# atx_power_control.net
KiCad netlist of a schematic drawn in EAGLE
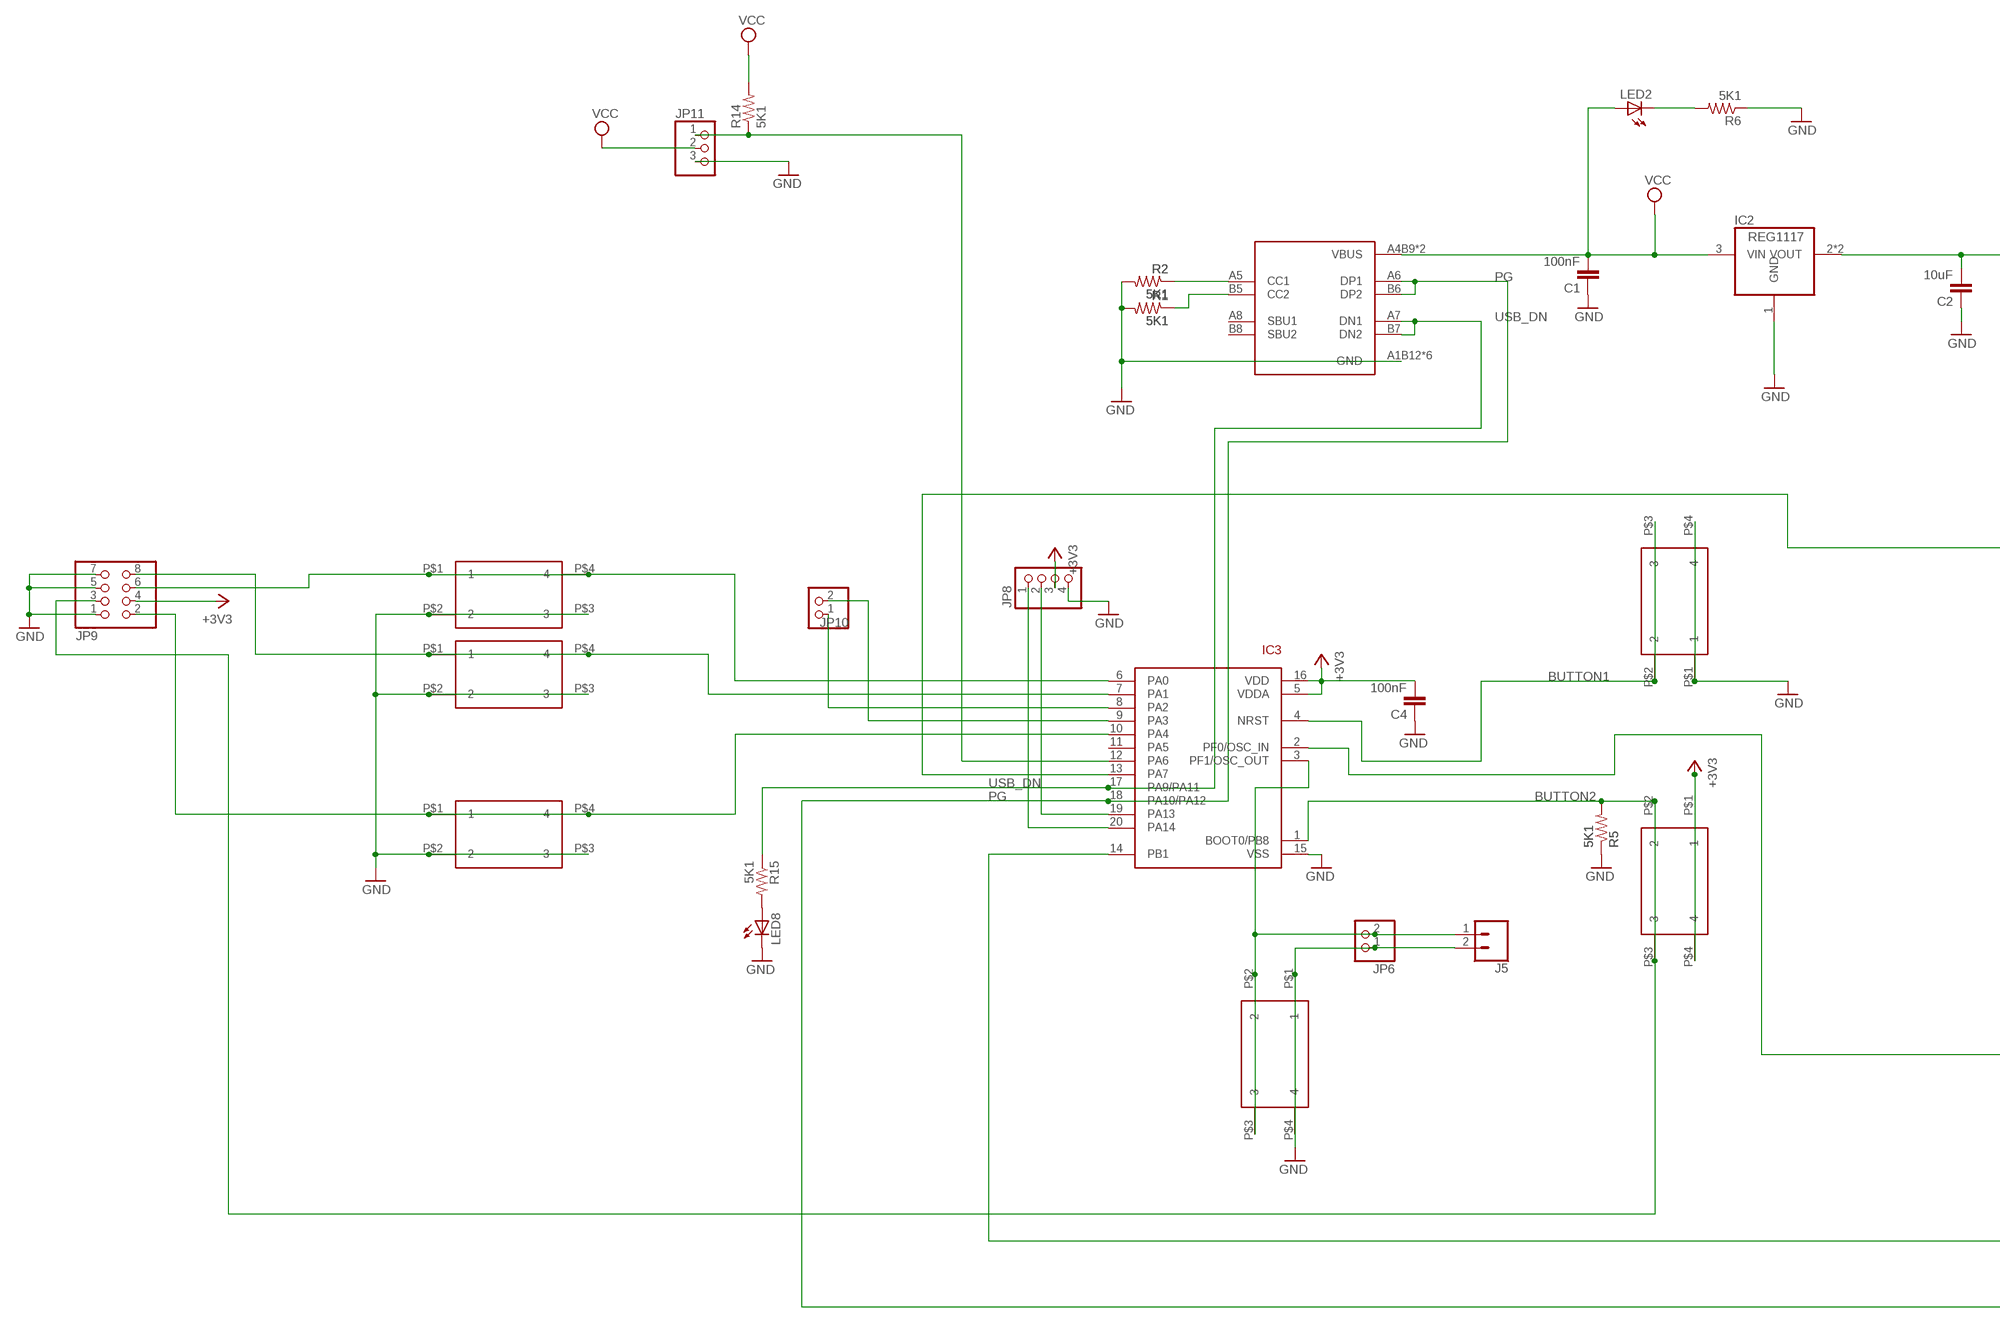
[diagram p0: schematic, sheet 1, part 1 of 2]
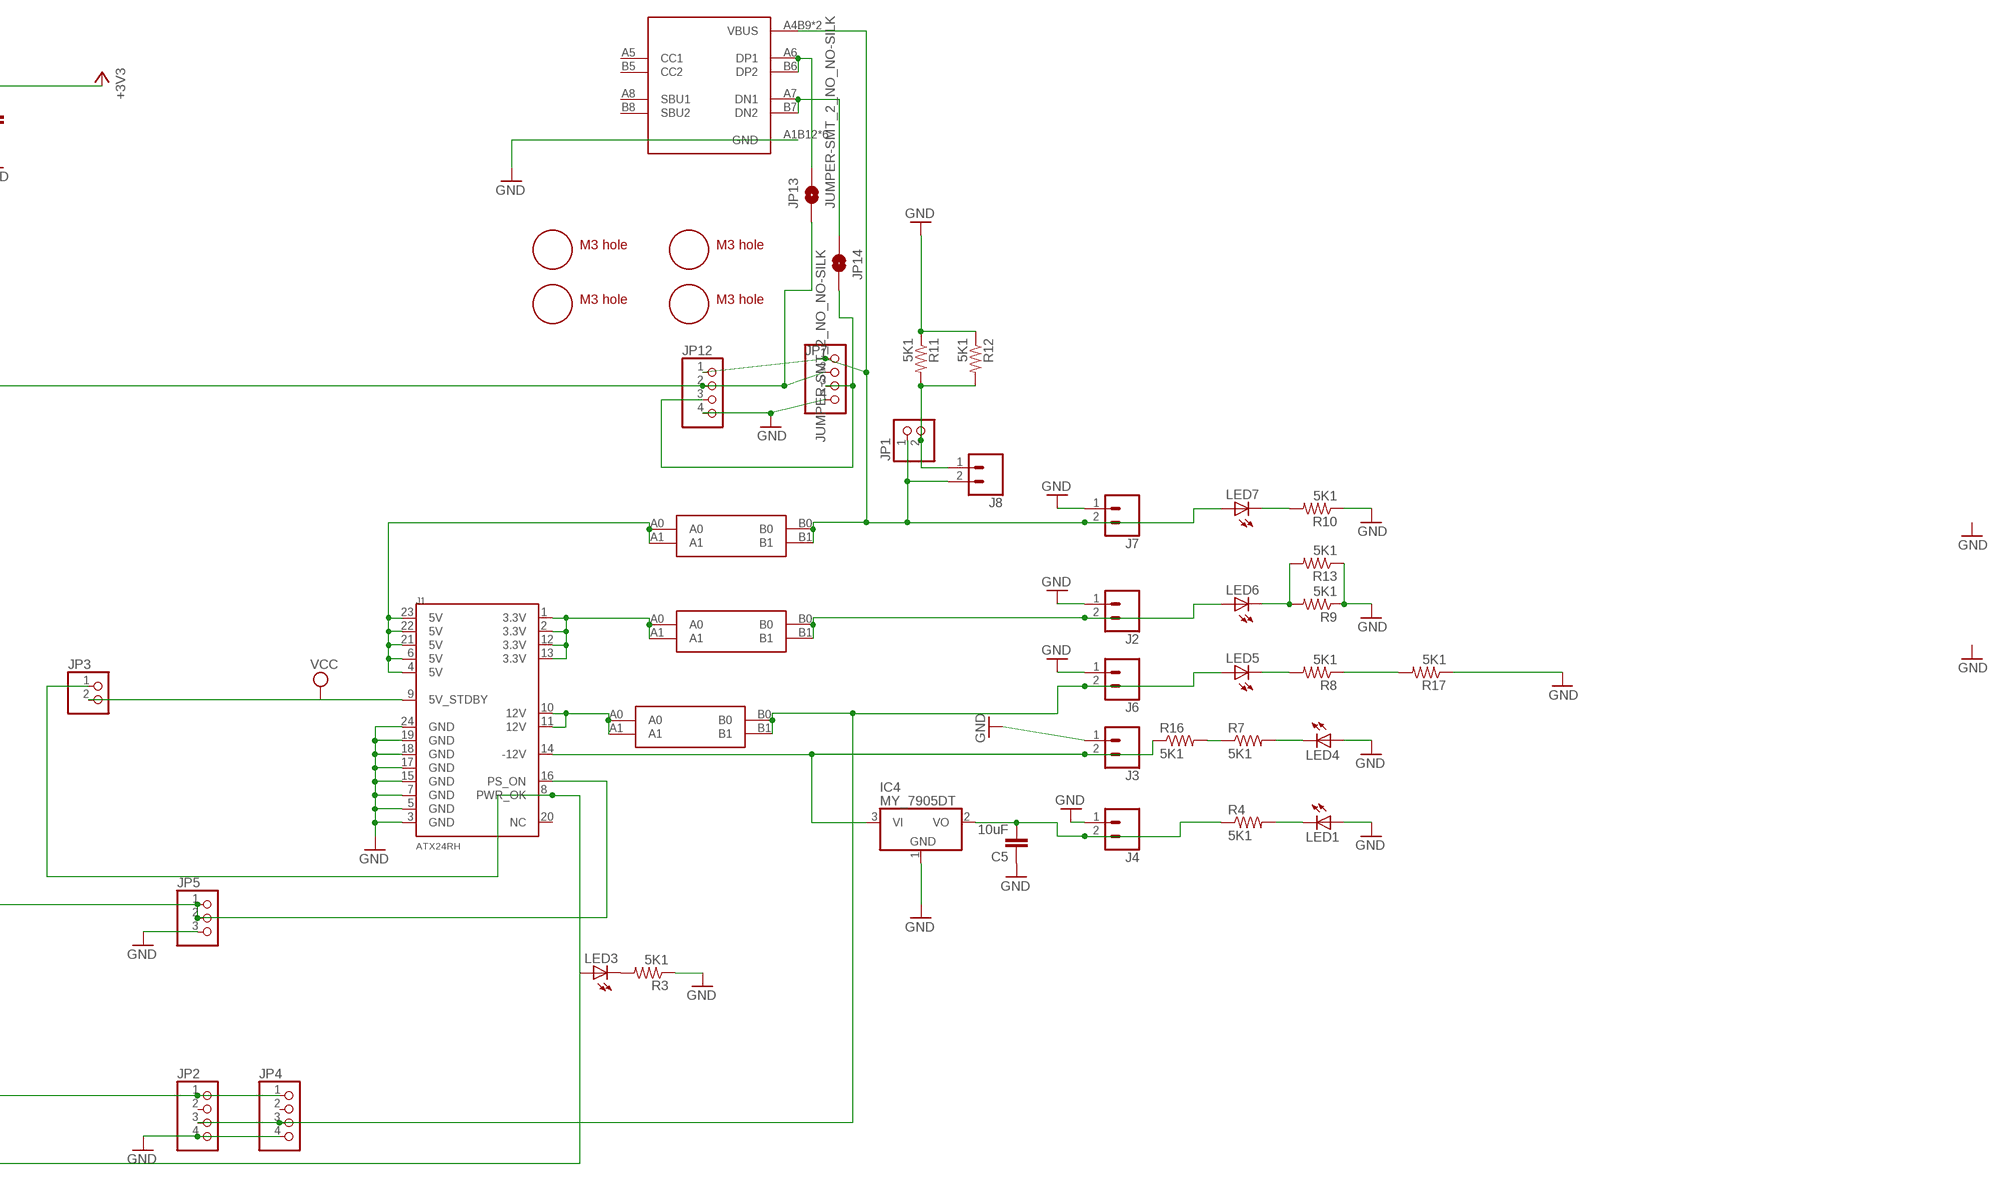
[diagram p1: schematic, sheet 1, part 2 of 2]

(export (version "E")
  (design (tool "Eeschema 10.0.6"))
  (components
    (comp (ref "C1")
      (value "100nF")
      (footprint "eagle-import:0805$1")
      (libsource (lib "eagle-import") (part "CAP0805"))
    )
    (comp (ref "C2")
      (value "10uF")
      (footprint "eagle-import:0805$1")
      (libsource (lib "eagle-import") (part "CAP0805"))
    )
    (comp (ref "C4")
      (value "100nF")
      (footprint "eagle-import:0805$1")
      (libsource (lib "eagle-import") (part "CAP0805"))
    )
    (comp (ref "C5")
      (value "10uF")
      (footprint "eagle-import:0805$1")
      (libsource (lib "eagle-import") (part "CAP0805"))
    )
    (comp (ref "IC2")
      (value "REG1117")
      (footprint "eagle-import:SOT223")
      (fields (field (name "MF") "TEXAS INSTRUMENTS") (field (name "MPN") "REG1117FAKTTT"))
      (libsource (lib "eagle-import") (part "REG1117"))
    )
    (comp (ref "IC3")
      (value "STM32F042F4")
      (footprint "eagle-import:TSSOP20")
      (libsource (lib "eagle-import") (part "STM32F042F4"))
    )
    (comp (ref "IC4")
      (value "MY_7905DT")
      (footprint "eagle-import:ADAFRUIT_TO252")
      (libsource (lib "eagle-import") (part "MY_7905DT"))
    )
    (comp (ref "J1")
      (value "ATX24RH")
      (footprint "eagle-import:ATX24_RIGHT_ANGLE")
      (libsource (lib "eagle-import") (part "ATX24RH"))
    )
    (comp (ref "J2")
      (value "CONN_023.5MM")
      (footprint "eagle-import:SCREWTERMINAL-3.5MM-2")
      (libsource (lib "eagle-import") (part "CONN_023.5MM"))
    )
    (comp (ref "J3")
      (value "CONN_023.5MM")
      (footprint "eagle-import:SCREWTERMINAL-3.5MM-2")
      (libsource (lib "eagle-import") (part "CONN_023.5MM"))
    )
    (comp (ref "J4")
      (value "CONN_023.5MM")
      (footprint "eagle-import:SCREWTERMINAL-3.5MM-2")
      (libsource (lib "eagle-import") (part "CONN_023.5MM"))
    )
    (comp (ref "J5")
      (value "CONN_023.5MM")
      (footprint "eagle-import:SCREWTERMINAL-3.5MM-2")
      (libsource (lib "eagle-import") (part "CONN_023.5MM"))
    )
    (comp (ref "J6")
      (value "CONN_023.5MM")
      (footprint "eagle-import:SCREWTERMINAL-3.5MM-2")
      (libsource (lib "eagle-import") (part "CONN_023.5MM"))
    )
    (comp (ref "J7")
      (value "CONN_023.5MM-NO_SILK")
      (footprint "eagle-import:SCREWTERMINAL-3.5MM-2-NS")
      (libsource (lib "eagle-import") (part "CONN_023.5MM-NO_SILK"))
    )
    (comp (ref "J8")
      (value "CONN_023.5MM")
      (footprint "eagle-import:SCREWTERMINAL-3.5MM-2")
      (libsource (lib "eagle-import") (part "CONN_023.5MM"))
    )
    (comp (ref "JP1")
      (value "PINHD-1X2")
      (footprint "eagle-import:1X02")
      (libsource (lib "eagle-import") (part "pinhead_325_PINHD-1X2"))
    )
    (comp (ref "JP2")
      (value "PINHD-1X4")
      (footprint "eagle-import:1X04")
      (libsource (lib "eagle-import") (part "PINHD-1X4"))
    )
    (comp (ref "JP3")
      (value "PINHD-1X2")
      (footprint "eagle-import:1X02")
      (libsource (lib "eagle-import") (part "pinhead_325_PINHD-1X2"))
    )
    (comp (ref "JP4")
      (value "PINHD-1X4")
      (footprint "eagle-import:1X04")
      (libsource (lib "eagle-import") (part "PINHD-1X4"))
    )
    (comp (ref "JP5")
      (value "PINHD-1X3:1")
      (footprint "eagle-import:1X03")
      (libsource (lib "eagle-import") (part "PINHD-1X3?{colon}1"))
    )
    (comp (ref "JP6")
      (value "PINHD-1X2")
      (footprint "eagle-import:1X02")
      (libsource (lib "eagle-import") (part "PINHD-1X2"))
    )
    (comp (ref "JP7")
      (value "PINHD-1X6")
      (footprint "eagle-import:1X06")
      (libsource (lib "eagle-import") (part "PINHD-1X6"))
    )
    (comp (ref "JP8")
      (value "PINHD-1X4")
      (footprint "eagle-import:1X04")
      (libsource (lib "eagle-import") (part "PINHD-1X4"))
    )
    (comp (ref "JP9")
      (value "PINHD-2X4")
      (footprint "eagle-import:2X04")
      (libsource (lib "eagle-import") (part "PINHD-2X4"))
    )
    (comp (ref "JP10")
      (value "PINHD-1X2")
      (footprint "eagle-import:1X02")
      (libsource (lib "eagle-import") (part "pinhead_325_PINHD-1X2"))
    )
    (comp (ref "JP11")
      (value "PINHD-1X3CB")
      (footprint "eagle-import:1X03-CLEANBIG")
      (libsource (lib "eagle-import") (part "PINHD-1X3CB"))
    )
    (comp (ref "JP12")
      (value "PINHD-1X6")
      (footprint "eagle-import:1X06")
      (libsource (lib "eagle-import") (part "PINHD-1X6"))
    )
    (comp (ref "JP13")
      (value "JUMPER-SMT_2_NO_NO-SILK")
      (footprint "eagle-import:SMT-JUMPER_2_NO_NO-SILK")
      (libsource (lib "eagle-import") (part "JUMPER-SMT_2_NO_NO-SILK"))
    )
    (comp (ref "JP14")
      (value "JUMPER-SMT_2_NO_NO-SILK")
      (footprint "eagle-import:SMT-JUMPER_2_NO_NO-SILK")
      (libsource (lib "eagle-import") (part "JUMPER-SMT_2_NO_NO-SILK"))
    )
    (comp (ref "LED1")
      (value "LEDCHIP-LED0805")
      (footprint "eagle-import:CHIP-LED0805")
      (libsource (lib "eagle-import") (part "LEDCHIP-LED0805"))
    )
    (comp (ref "LED2")
      (value "LEDCHIP-LED0805")
      (footprint "eagle-import:CHIP-LED0805")
      (libsource (lib "eagle-import") (part "LEDCHIP-LED0805"))
    )
    (comp (ref "LED3")
      (value "LEDCHIP-LED0805")
      (footprint "eagle-import:CHIP-LED0805")
      (libsource (lib "eagle-import") (part "LEDCHIP-LED0805"))
    )
    (comp (ref "LED4")
      (value "LEDCHIP-LED0805")
      (footprint "eagle-import:CHIP-LED0805")
      (libsource (lib "eagle-import") (part "LEDCHIP-LED0805"))
    )
    (comp (ref "LED5")
      (value "LEDCHIP-LED0805")
      (footprint "eagle-import:CHIP-LED0805")
      (libsource (lib "eagle-import") (part "LEDCHIP-LED0805"))
    )
    (comp (ref "LED6")
      (value "LEDCHIP-LED0805")
      (footprint "eagle-import:CHIP-LED0805")
      (libsource (lib "eagle-import") (part "LEDCHIP-LED0805"))
    )
    (comp (ref "LED7")
      (value "LEDCHIP-LED0805")
      (footprint "eagle-import:CHIP-LED0805")
      (libsource (lib "eagle-import") (part "LEDCHIP-LED0805"))
    )
    (comp (ref "LED8")
      (value "LEDCHIP-LED0805")
      (footprint "eagle-import:CHIP-LED0805")
      (libsource (lib "eagle-import") (part "LEDCHIP-LED0805"))
    )
    (comp (ref "R1")
      (value "5K1")
      (footprint "eagle-import:0805")
      (libsource (lib "eagle-import") (part "atx_power_control_RESISTOR0805-RES"))
    )
    (comp (ref "R2")
      (value "5K1")
      (footprint "eagle-import:0805")
      (libsource (lib "eagle-import") (part "atx_power_control_RESISTOR0805-RES"))
    )
    (comp (ref "R3")
      (value "5K1")
      (footprint "eagle-import:0805")
      (libsource (lib "eagle-import") (part "atx_power_control_RESISTOR0805-RES"))
    )
    (comp (ref "R4")
      (value "5K1")
      (footprint "eagle-import:0805")
      (libsource (lib "eagle-import") (part "RESISTOR0805-RES"))
    )
    (comp (ref "R5")
      (value "5K1")
      (footprint "eagle-import:0805")
      (libsource (lib "eagle-import") (part "atx_power_control_RESISTOR0805-RES"))
    )
    (comp (ref "R6")
      (value "5K1")
      (footprint "eagle-import:0805")
      (libsource (lib "eagle-import") (part "atx_power_control_RESISTOR0805-RES"))
    )
    (comp (ref "R7")
      (value "5K1")
      (footprint "eagle-import:0805")
      (libsource (lib "eagle-import") (part "RESISTOR0805-RES"))
    )
    (comp (ref "R8")
      (value "5K1")
      (footprint "eagle-import:0805")
      (libsource (lib "eagle-import") (part "atx_power_control_RESISTOR0805-RES"))
    )
    (comp (ref "R9")
      (value "5K1")
      (footprint "eagle-import:0805")
      (libsource (lib "eagle-import") (part "atx_power_control_RESISTOR0805-RES"))
    )
    (comp (ref "R10")
      (value "5K1")
      (footprint "eagle-import:0805")
      (libsource (lib "eagle-import") (part "atx_power_control_RESISTOR0805-RES"))
    )
    (comp (ref "R11")
      (value "5K1")
      (footprint "eagle-import:0805")
      (libsource (lib "eagle-import") (part "atx_power_control_RESISTOR0805-RES"))
    )
    (comp (ref "R12")
      (value "5K1")
      (footprint "eagle-import:0805")
      (libsource (lib "eagle-import") (part "atx_power_control_RESISTOR0805-RES"))
    )
    (comp (ref "R13")
      (value "5K1")
      (footprint "eagle-import:0805")
      (libsource (lib "eagle-import") (part "atx_power_control_RESISTOR0805-RES"))
    )
    (comp (ref "R14")
      (value "5K1")
      (footprint "eagle-import:0805")
      (libsource (lib "eagle-import") (part "atx_power_control_RESISTOR0805-RES"))
    )
    (comp (ref "R15")
      (value "5K1")
      (footprint "eagle-import:0805")
      (libsource (lib "eagle-import") (part "atx_power_control_RESISTOR0805-RES"))
    )
    (comp (ref "R16")
      (value "5K1")
      (footprint "eagle-import:0805")
      (libsource (lib "eagle-import") (part "RESISTOR0805-RES"))
    )
    (comp (ref "R17")
      (value "5K1")
      (footprint "eagle-import:0805")
      (libsource (lib "eagle-import") (part "atx_power_control_RESISTOR0805-RES"))
    )
    (comp (ref "SW1")
      (value "324_SW")
      (footprint "eagle-import:342_SWICH_FOOT")
      (libsource (lib "eagle-import") (part "324_SW"))
    )
    (comp (ref "SW2")
      (value "324_SW")
      (footprint "eagle-import:342_SWICH_FOOT")
      (libsource (lib "eagle-import") (part "324_SW"))
    )
    (comp (ref "SW3")
      (value "324_SW")
      (footprint "eagle-import:342_SWICH_FOOT")
      (libsource (lib "eagle-import") (part "324_SW"))
    )
    (comp (ref "SW4")
      (value "324_SW")
      (footprint "eagle-import:342_SWICH_FOOT")
      (libsource (lib "eagle-import") (part "324_SW"))
    )
    (comp (ref "SW5")
      (value "324_SW")
      (footprint "eagle-import:342_SWICH_FOOT")
      (libsource (lib "eagle-import") (part "324_SW"))
    )
    (comp (ref "SW7")
      (value "324_SW")
      (footprint "eagle-import:342_SWICH_FOOT")
      (libsource (lib "eagle-import") (part "324_SW"))
    )
    (comp (ref "U$1")
      (value "M3_MOUNTING_HOLE")
      (footprint "eagle-import:M3_MOUNTING_HOLE_PACK")
      (libsource (lib "eagle-import") (part "M3_MOUNTING_HOLE"))
    )
    (comp (ref "U$2")
      (value "M3_MOUNTING_HOLE")
      (footprint "eagle-import:M3_MOUNTING_HOLE_PACK")
      (libsource (lib "eagle-import") (part "M3_MOUNTING_HOLE"))
    )
    (comp (ref "U$3")
      (value "M3_MOUNTING_HOLE")
      (footprint "eagle-import:M3_MOUNTING_HOLE_PACK")
      (libsource (lib "eagle-import") (part "M3_MOUNTING_HOLE"))
    )
    (comp (ref "U$5")
      (value "CAR_FUSE_HOLDER3IN1")
      (footprint "eagle-import:FUSE_HOLDER_3IN1")
      (libsource (lib "eagle-import") (part "CAR_FUSE_HOLDER3IN1"))
    )
    (comp (ref "U$7")
      (value "CAR_FUSE_HOLDER3IN1")
      (footprint "eagle-import:FUSE_HOLDER_3IN1")
      (libsource (lib "eagle-import") (part "CAR_FUSE_HOLDER3IN1"))
    )
    (comp (ref "U$8")
      (value "CAR_FUSE_HOLDER3IN1")
      (footprint "eagle-import:FUSE_HOLDER_3IN1")
      (libsource (lib "eagle-import") (part "CAR_FUSE_HOLDER3IN1"))
    )
    (comp (ref "U$10")
      (value "M3_MOUNTING_HOLE")
      (footprint "eagle-import:M3_MOUNTING_HOLE_PACK")
      (libsource (lib "eagle-import") (part "M3_MOUNTING_HOLE"))
    )
    (comp (ref "U1")
      (value "USBC_16P")
      (footprint "eagle-import:USBC_16P_FOOT")
      (libsource (lib "eagle-import") (part "USBC_16P"))
    )
    (comp (ref "U2")
      (value "USBC_16P")
      (footprint "eagle-import:USBC_16P_FOOT")
      (libsource (lib "eagle-import") (part "USBC_16P"))
    )
  )
  (nets
    (net (code "1") (name "+3V3") (class "Default")
      (node (ref "C2") (pin "2") (pinfunction "2_2") (pintype "passive"))
      (node (ref "C4") (pin "2") (pinfunction "2_2") (pintype "passive"))
      (node (ref "IC2") (pin "2") (pinfunction "VOUT_2") (pintype "output"))
      (node (ref "IC2") (pin "4") (pinfunction "VOUT_4") (pintype "output"))
      (node (ref "IC3") (pin "16") (pinfunction "VDD_16") (pintype "bidirectional"))
      (node (ref "IC3") (pin "5") (pinfunction "VDDA_5") (pintype "bidirectional"))
      (node (ref "JP8") (pin "3") (pinfunction "3_3") (pintype "passive"))
      (node (ref "JP9") (pin "4") (pinfunction "4_4") (pintype "passive"))
      (node (ref "SW4") (pin "P$1") (pinfunction "1_P$1") (pintype "bidirectional"))
      (node (ref "SW4") (pin "P$4") (pinfunction "4_P$4") (pintype "bidirectional"))
    )
    (net (code "2") (name "/BUTTON1") (class "Default")
      (node (ref "IC3") (pin "4") (pinfunction "NRST_4") (pintype "bidirectional"))
      (node (ref "SW3") (pin "P$2") (pinfunction "2_P$2") (pintype "bidirectional"))
      (node (ref "SW3") (pin "P$3") (pinfunction "3_P$3") (pintype "bidirectional"))
    )
    (net (code "3") (name "/BUTTON2") (class "Default")
      (node (ref "IC3") (pin "1") (pinfunction "BOOT0/PB8_1") (pintype "bidirectional"))
      (node (ref "JP9") (pin "3") (pinfunction "3_3") (pintype "passive"))
      (node (ref "R5") (pin "2") (pinfunction "2_2") (pintype "passive"))
      (node (ref "SW4") (pin "P$2") (pinfunction "2_P$2") (pintype "bidirectional"))
      (node (ref "SW4") (pin "P$3") (pinfunction "3_P$3") (pintype "bidirectional"))
    )
    (net (code "4") (name "/PG") (class "Default")
      (node (ref "IC3") (pin "18") (pinfunction "PA10/PA12_18") (pintype "bidirectional"))
      (node (ref "J1") (pin "8") (pinfunction "PWR_OK_8") (pintype "bidirectional"))
      (node (ref "JP3") (pin "1") (pinfunction "1_1") (pintype "passive"))
      (node (ref "LED3") (pin "A") (pinfunction "A_A") (pintype "passive"))
      (node (ref "U2") (pin "A6") (pinfunction "DP1_A6") (pintype "bidirectional"))
      (node (ref "U2") (pin "B6") (pinfunction "DP2_B6") (pintype "bidirectional"))
    )
    (net (code "5") (name "/USB_DN") (class "Default")
      (node (ref "IC3") (pin "17") (pinfunction "PA9/PA11_17") (pintype "bidirectional"))
      (node (ref "R15") (pin "1") (pinfunction "1_1") (pintype "passive"))
      (node (ref "U2") (pin "A7") (pinfunction "DN1_A7") (pintype "bidirectional"))
      (node (ref "U2") (pin "B7") (pinfunction "DN2_B7") (pintype "bidirectional"))
    )
    (net (code "6") (name "GND") (class "Default")
      (node (ref "C1") (pin "1") (pinfunction "1_1") (pintype "passive"))
      (node (ref "C2") (pin "1") (pinfunction "1_1") (pintype "passive"))
      (node (ref "C4") (pin "1") (pinfunction "1_1") (pintype "passive"))
      (node (ref "C5") (pin "1") (pinfunction "1_1") (pintype "passive"))
      (node (ref "IC2") (pin "1") (pinfunction "GND_1") (pintype "power_in"))
      (node (ref "IC3") (pin "15") (pinfunction "VSS_15") (pintype "bidirectional"))
      (node (ref "IC4") (pin "1") (pinfunction "GND_1") (pintype "passive"))
      (node (ref "J1") (pin "15") (pinfunction "GND_15") (pintype "bidirectional"))
      (node (ref "J1") (pin "17") (pinfunction "GND_17") (pintype "bidirectional"))
      (node (ref "J1") (pin "18") (pinfunction "GND_18") (pintype "bidirectional"))
      (node (ref "J1") (pin "19") (pinfunction "GND_19") (pintype "bidirectional"))
      (node (ref "J1") (pin "24") (pinfunction "GND_24") (pintype "bidirectional"))
      (node (ref "J1") (pin "3") (pinfunction "GND_3") (pintype "bidirectional"))
      (node (ref "J1") (pin "5") (pinfunction "GND_5") (pintype "bidirectional"))
      (node (ref "J1") (pin "7") (pinfunction "GND_7") (pintype "bidirectional"))
      (node (ref "J2") (pin "1") (pinfunction "1_1") (pintype "passive"))
      (node (ref "J3") (pin "1") (pinfunction "1_1") (pintype "passive"))
      (node (ref "J4") (pin "1") (pinfunction "1_1") (pintype "passive"))
      (node (ref "J5") (pin "2") (pinfunction "2_2") (pintype "passive"))
      (node (ref "J6") (pin "1") (pinfunction "1_1") (pintype "passive"))
      (node (ref "J7") (pin "1") (pinfunction "1_1") (pintype "passive"))
      (node (ref "JP11") (pin "3") (pinfunction "3_3") (pintype "passive"))
      (node (ref "JP12") (pin "4") (pinfunction "4_4") (pintype "passive"))
      (node (ref "JP2") (pin "4") (pinfunction "4_4") (pintype "passive"))
      (node (ref "JP4") (pin "4") (pinfunction "4_4") (pintype "passive"))
      (node (ref "JP5") (pin "3") (pinfunction "3_3") (pintype "passive"))
      (node (ref "JP6") (pin "1") (pinfunction "1_1") (pintype "passive"))
      (node (ref "JP7") (pin "4") (pinfunction "4_4") (pintype "passive"))
      (node (ref "JP8") (pin "4") (pinfunction "4_4") (pintype "passive"))
      (node (ref "JP9") (pin "1") (pinfunction "1_1") (pintype "passive"))
      (node (ref "JP9") (pin "5") (pinfunction "5_5") (pintype "passive"))
      (node (ref "JP9") (pin "7") (pinfunction "7_7") (pintype "passive"))
      (node (ref "LED1") (pin "A") (pinfunction "A_A") (pintype "passive"))
      (node (ref "LED4") (pin "A") (pinfunction "A_A") (pintype "passive"))
      (node (ref "LED8") (pin "C") (pinfunction "C_C") (pintype "passive"))
      (node (ref "R1") (pin "2") (pinfunction "2_2") (pintype "passive"))
      (node (ref "R10") (pin "1") (pinfunction "1_1") (pintype "passive"))
      (node (ref "R11") (pin "1") (pinfunction "1_1") (pintype "passive"))
      (node (ref "R12") (pin "1") (pinfunction "1_1") (pintype "passive"))
      (node (ref "R13") (pin "1") (pinfunction "1_1") (pintype "passive"))
      (node (ref "R17") (pin "1") (pinfunction "1_1") (pintype "passive"))
      (node (ref "R2") (pin "2") (pinfunction "2_2") (pintype "passive"))
      (node (ref "R3") (pin "1") (pinfunction "1_1") (pintype "passive"))
      (node (ref "R5") (pin "1") (pinfunction "1_1") (pintype "passive"))
      (node (ref "R6") (pin "1") (pinfunction "1_1") (pintype "passive"))
      (node (ref "R9") (pin "1") (pinfunction "1_1") (pintype "passive"))
      (node (ref "SW1") (pin "P$1") (pinfunction "1_P$1") (pintype "bidirectional"))
      (node (ref "SW1") (pin "P$4") (pinfunction "4_P$4") (pintype "bidirectional"))
      (node (ref "SW2") (pin "P$2") (pinfunction "2_P$2") (pintype "bidirectional"))
      (node (ref "SW2") (pin "P$3") (pinfunction "3_P$3") (pintype "bidirectional"))
      (node (ref "SW3") (pin "P$1") (pinfunction "1_P$1") (pintype "bidirectional"))
      (node (ref "SW3") (pin "P$4") (pinfunction "4_P$4") (pintype "bidirectional"))
      (node (ref "SW5") (pin "P$2") (pinfunction "2_P$2") (pintype "bidirectional"))
      (node (ref "SW5") (pin "P$3") (pinfunction "3_P$3") (pintype "bidirectional"))
      (node (ref "SW7") (pin "P$2") (pinfunction "2_P$2") (pintype "bidirectional"))
      (node (ref "SW7") (pin "P$3") (pinfunction "3_P$3") (pintype "bidirectional"))
      (node (ref "U1") (pin "A1B12") (pinfunction "GND_A1B12") (pintype "bidirectional"))
      (node (ref "U1") (pin "B11A12") (pinfunction "GND_B11A12") (pintype "bidirectional"))
      (node (ref "U1") (pin "P$13") (pinfunction "GND_P$13") (pintype "bidirectional"))
      (node (ref "U1") (pin "P$14") (pinfunction "GND_P$14") (pintype "bidirectional"))
      (node (ref "U1") (pin "P$15") (pinfunction "GND_P$15") (pintype "bidirectional"))
      (node (ref "U1") (pin "P$16") (pinfunction "GND_P$16") (pintype "bidirectional"))
      (node (ref "U2") (pin "A1B12") (pinfunction "GND_A1B12") (pintype "bidirectional"))
      (node (ref "U2") (pin "B11A12") (pinfunction "GND_B11A12") (pintype "bidirectional"))
      (node (ref "U2") (pin "P$13") (pinfunction "GND_P$13") (pintype "bidirectional"))
      (node (ref "U2") (pin "P$14") (pinfunction "GND_P$14") (pintype "bidirectional"))
      (node (ref "U2") (pin "P$15") (pinfunction "GND_P$15") (pintype "bidirectional"))
      (node (ref "U2") (pin "P$16") (pinfunction "GND_P$16") (pintype "bidirectional"))
    )
    (net (code "7") (name "Net-(IC3-PA0)") (class "Default")
      (node (ref "IC3") (pin "6") (pinfunction "PA0_6") (pintype "bidirectional"))
      (node (ref "JP9") (pin "6") (pinfunction "6_6") (pintype "passive"))
      (node (ref "SW2") (pin "P$1") (pinfunction "1_P$1") (pintype "bidirectional"))
      (node (ref "SW2") (pin "P$4") (pinfunction "4_P$4") (pintype "bidirectional"))
    )
    (net (code "8") (name "Net-(IC3-PA1)") (class "Default")
      (node (ref "IC3") (pin "7") (pinfunction "PA1_7") (pintype "bidirectional"))
      (node (ref "JP9") (pin "8") (pinfunction "8_8") (pintype "passive"))
      (node (ref "SW5") (pin "P$1") (pinfunction "1_P$1") (pintype "bidirectional"))
      (node (ref "SW5") (pin "P$4") (pinfunction "4_P$4") (pintype "bidirectional"))
    )
    (net (code "9") (name "Net-(IC3-PA2)") (class "Default")
      (node (ref "IC3") (pin "8") (pinfunction "PA2_8") (pintype "bidirectional"))
      (node (ref "JP10") (pin "1") (pinfunction "1_1") (pintype "passive"))
    )
    (net (code "10") (name "Net-(IC3-PA3)") (class "Default")
      (node (ref "IC3") (pin "9") (pinfunction "PA3_9") (pintype "bidirectional"))
      (node (ref "JP10") (pin "2") (pinfunction "2_2") (pintype "passive"))
    )
    (net (code "11") (name "Net-(IC3-PA4)") (class "Default")
      (node (ref "IC3") (pin "10") (pinfunction "PA4_10") (pintype "bidirectional"))
      (node (ref "JP9") (pin "2") (pinfunction "2_2") (pintype "passive"))
      (node (ref "SW7") (pin "P$1") (pinfunction "1_P$1") (pintype "bidirectional"))
      (node (ref "SW7") (pin "P$4") (pinfunction "4_P$4") (pintype "bidirectional"))
    )
    (net (code "12") (name "Net-(IC3-PA6)") (class "Default")
      (node (ref "IC3") (pin "12") (pinfunction "PA6_12") (pintype "bidirectional"))
      (node (ref "JP11") (pin "1") (pinfunction "1_1") (pintype "passive"))
      (node (ref "R14") (pin "1") (pinfunction "1_1") (pintype "passive"))
    )
    (net (code "13") (name "Net-(IC3-PA7)") (class "Default")
      (node (ref "IC3") (pin "13") (pinfunction "PA7_13") (pintype "bidirectional"))
      (node (ref "JP12") (pin "2") (pinfunction "2_2") (pintype "passive"))
      (node (ref "JP13") (pin "1") (pinfunction "1_1") (pintype "passive"))
      (node (ref "JP7") (pin "2") (pinfunction "2_2") (pintype "passive"))
    )
    (net (code "14") (name "Net-(IC3-PA13)") (class "Default")
      (node (ref "IC3") (pin "19") (pinfunction "PA13_19") (pintype "bidirectional"))
      (node (ref "JP8") (pin "2") (pinfunction "2_2") (pintype "passive"))
    )
    (net (code "15") (name "Net-(IC3-PA14)") (class "Default")
      (node (ref "IC3") (pin "20") (pinfunction "PA14_20") (pintype "bidirectional"))
      (node (ref "JP8") (pin "1") (pinfunction "1_1") (pintype "passive"))
    )
    (net (code "16") (name "Net-(IC3-PB1)") (class "Default")
      (node (ref "IC3") (pin "14") (pinfunction "PB1_14") (pintype "bidirectional"))
      (node (ref "JP2") (pin "1") (pinfunction "1_1") (pintype "passive"))
      (node (ref "JP4") (pin "1") (pinfunction "1_1") (pintype "passive"))
    )
    (net (code "17") (name "Net-(IC3-PF0{slash}OSC_IN)") (class "Default")
      (node (ref "IC3") (pin "2") (pinfunction "PF0/OSC_IN_2") (pintype "bidirectional"))
      (node (ref "J1") (pin "16") (pinfunction "PS_ON_16") (pintype "bidirectional"))
      (node (ref "JP5") (pin "1") (pinfunction "1_1") (pintype "passive"))
      (node (ref "JP5") (pin "2") (pinfunction "2_2") (pintype "passive"))
    )
    (net (code "18") (name "Net-(IC3-PF1{slash}OSC_OUT)") (class "Default")
      (node (ref "IC3") (pin "3") (pinfunction "PF1/OSC_OUT_3") (pintype "bidirectional"))
      (node (ref "J5") (pin "1") (pinfunction "1_1") (pintype "passive"))
      (node (ref "JP6") (pin "2") (pinfunction "2_2") (pintype "passive"))
      (node (ref "SW1") (pin "P$2") (pinfunction "2_P$2") (pintype "bidirectional"))
      (node (ref "SW1") (pin "P$3") (pinfunction "3_P$3") (pintype "bidirectional"))
    )
    (net (code "19") (name "Net-(IC4-VI)") (class "Default")
      (node (ref "IC4") (pin "3") (pinfunction "VI_3") (pintype "input"))
      (node (ref "J1") (pin "14") (pinfunction "-12V_14") (pintype "bidirectional"))
      (node (ref "J3") (pin "2") (pinfunction "2_2") (pintype "passive"))
      (node (ref "R16") (pin "1") (pinfunction "1_1") (pintype "passive"))
    )
    (net (code "20") (name "Net-(IC4-VO)") (class "Default")
      (node (ref "C5") (pin "2") (pinfunction "2_2") (pintype "passive"))
      (node (ref "IC4") (pin "2") (pinfunction "VO_2") (pintype "passive"))
      (node (ref "J4") (pin "2") (pinfunction "2_2") (pintype "passive"))
      (node (ref "R4") (pin "1") (pinfunction "1_1") (pintype "passive"))
    )
    (net (code "21") (name "Net-(J1-3.3V-Pad1)") (class "Default")
      (node (ref "J1") (pin "1") (pinfunction "3.3V_1") (pintype "bidirectional"))
      (node (ref "J1") (pin "12") (pinfunction "3.3V_12") (pintype "bidirectional"))
      (node (ref "J1") (pin "13") (pinfunction "3.3V_13") (pintype "bidirectional"))
      (node (ref "J1") (pin "2") (pinfunction "3.3V_2") (pintype "bidirectional"))
      (node (ref "U$7") (pin "A0") (pinfunction "A0_A0") (pintype "bidirectional"))
      (node (ref "U$7") (pin "A1") (pinfunction "A1_A1") (pintype "bidirectional"))
    )
    (net (code "22") (name "Net-(J1-5V-Pad21)") (class "Default")
      (node (ref "J1") (pin "21") (pinfunction "5V_21") (pintype "bidirectional"))
      (node (ref "J1") (pin "22") (pinfunction "5V_22") (pintype "bidirectional"))
      (node (ref "J1") (pin "23") (pinfunction "5V_23") (pintype "bidirectional"))
      (node (ref "J1") (pin "4") (pinfunction "5V_4") (pintype "bidirectional"))
      (node (ref "J1") (pin "6") (pinfunction "5V_6") (pintype "bidirectional"))
      (node (ref "U$8") (pin "A0") (pinfunction "A0_A0") (pintype "bidirectional"))
      (node (ref "U$8") (pin "A1") (pinfunction "A1_A1") (pintype "bidirectional"))
    )
    (net (code "23") (name "Net-(J1-12V-Pad10)") (class "Default")
      (node (ref "J1") (pin "10") (pinfunction "12V_10") (pintype "bidirectional"))
      (node (ref "J1") (pin "11") (pinfunction "12V_11") (pintype "bidirectional"))
      (node (ref "U$5") (pin "A0") (pinfunction "A0_A0") (pintype "bidirectional"))
      (node (ref "U$5") (pin "A1") (pinfunction "A1_A1") (pintype "bidirectional"))
    )
    (net (code "24") (name "Net-(J2-Pad2)") (class "Default")
      (node (ref "J2") (pin "2") (pinfunction "2_2") (pintype "passive"))
      (node (ref "LED6") (pin "A") (pinfunction "A_A") (pintype "passive"))
      (node (ref "U$7") (pin "B0") (pinfunction "B0_B0") (pintype "bidirectional"))
      (node (ref "U$7") (pin "B1") (pinfunction "B1_B1") (pintype "bidirectional"))
    )
    (net (code "25") (name "Net-(J6-Pad2)") (class "Default")
      (node (ref "J6") (pin "2") (pinfunction "2_2") (pintype "passive"))
      (node (ref "JP2") (pin "3") (pinfunction "3_3") (pintype "passive"))
      (node (ref "JP4") (pin "3") (pinfunction "3_3") (pintype "passive"))
      (node (ref "LED5") (pin "A") (pinfunction "A_A") (pintype "passive"))
      (node (ref "U$5") (pin "B0") (pinfunction "B0_B0") (pintype "bidirectional"))
      (node (ref "U$5") (pin "B1") (pinfunction "B1_B1") (pintype "bidirectional"))
    )
    (net (code "26") (name "Net-(J7-Pad2)") (class "Default")
      (node (ref "J7") (pin "2") (pinfunction "2_2") (pintype "passive"))
      (node (ref "J8") (pin "2") (pinfunction "2_2") (pintype "passive"))
      (node (ref "JP1") (pin "1") (pinfunction "1_1") (pintype "passive"))
      (node (ref "JP12") (pin "1") (pinfunction "1_1") (pintype "passive"))
      (node (ref "JP7") (pin "1") (pinfunction "1_1") (pintype "passive"))
      (node (ref "LED7") (pin "A") (pinfunction "A_A") (pintype "passive"))
      (node (ref "U$8") (pin "B0") (pinfunction "B0_B0") (pintype "bidirectional"))
      (node (ref "U$8") (pin "B1") (pinfunction "B1_B1") (pintype "bidirectional"))
      (node (ref "U1") (pin "A4B9") (pinfunction "VBUS_A4B9") (pintype "bidirectional"))
      (node (ref "U1") (pin "B4A9") (pinfunction "VBUS_B4A9") (pintype "bidirectional"))
    )
    (net (code "27") (name "Net-(J8-Pad1)") (class "Default")
      (node (ref "J8") (pin "1") (pinfunction "1_1") (pintype "passive"))
      (node (ref "JP1") (pin "2") (pinfunction "2_2") (pintype "passive"))
      (node (ref "R11") (pin "2") (pinfunction "2_2") (pintype "passive"))
      (node (ref "R12") (pin "2") (pinfunction "2_2") (pintype "passive"))
    )
    (net (code "28") (name "Net-(JP12-Pad3)") (class "Default")
      (node (ref "JP12") (pin "3") (pinfunction "3_3") (pintype "passive"))
      (node (ref "JP14") (pin "2") (pinfunction "2_2") (pintype "passive"))
      (node (ref "JP7") (pin "3") (pinfunction "3_3") (pintype "passive"))
    )
    (net (code "29") (name "Net-(LED1-PadC)") (class "Default")
      (node (ref "LED1") (pin "C") (pinfunction "C_C") (pintype "passive"))
      (node (ref "R4") (pin "2") (pinfunction "2_2") (pintype "passive"))
    )
    (net (code "30") (name "Net-(LED2-PadC)") (class "Default")
      (node (ref "LED2") (pin "C") (pinfunction "C_C") (pintype "passive"))
      (node (ref "R6") (pin "2") (pinfunction "2_2") (pintype "passive"))
    )
    (net (code "31") (name "Net-(LED3-PadC)") (class "Default")
      (node (ref "LED3") (pin "C") (pinfunction "C_C") (pintype "passive"))
      (node (ref "R3") (pin "2") (pinfunction "2_2") (pintype "passive"))
    )
    (net (code "32") (name "Net-(LED4-PadC)") (class "Default")
      (node (ref "LED4") (pin "C") (pinfunction "C_C") (pintype "passive"))
      (node (ref "R7") (pin "2") (pinfunction "2_2") (pintype "passive"))
    )
    (net (code "33") (name "Net-(LED5-PadC)") (class "Default")
      (node (ref "LED5") (pin "C") (pinfunction "C_C") (pintype "passive"))
      (node (ref "R8") (pin "2") (pinfunction "2_2") (pintype "passive"))
    )
    (net (code "34") (name "Net-(LED6-PadC)") (class "Default")
      (node (ref "LED6") (pin "C") (pinfunction "C_C") (pintype "passive"))
      (node (ref "R13") (pin "2") (pinfunction "2_2") (pintype "passive"))
      (node (ref "R9") (pin "2") (pinfunction "2_2") (pintype "passive"))
    )
    (net (code "35") (name "Net-(LED7-PadC)") (class "Default")
      (node (ref "LED7") (pin "C") (pinfunction "C_C") (pintype "passive"))
      (node (ref "R10") (pin "2") (pinfunction "2_2") (pintype "passive"))
    )
    (net (code "36") (name "Net-(LED8-PadA)") (class "Default")
      (node (ref "LED8") (pin "A") (pinfunction "A_A") (pintype "passive"))
      (node (ref "R15") (pin "2") (pinfunction "2_2") (pintype "passive"))
    )
    (net (code "37") (name "Net-(R16-Pad2)") (class "Default")
      (node (ref "R16") (pin "2") (pinfunction "2_2") (pintype "passive"))
      (node (ref "R7") (pin "1") (pinfunction "1_1") (pintype "passive"))
    )
    (net (code "38") (name "Net-(R17-Pad2)") (class "Default")
      (node (ref "R17") (pin "2") (pinfunction "2_2") (pintype "passive"))
      (node (ref "R8") (pin "1") (pinfunction "1_1") (pintype "passive"))
    )
    (net (code "39") (name "Net-(U1-DN1)") (class "Default")
      (node (ref "JP14") (pin "1") (pinfunction "1_1") (pintype "passive"))
      (node (ref "U1") (pin "A7") (pinfunction "DN1_A7") (pintype "bidirectional"))
      (node (ref "U1") (pin "B7") (pinfunction "DN2_B7") (pintype "bidirectional"))
    )
    (net (code "40") (name "Net-(U1-DP1)") (class "Default")
      (node (ref "JP13") (pin "2") (pinfunction "2_2") (pintype "passive"))
      (node (ref "U1") (pin "A6") (pinfunction "DP1_A6") (pintype "bidirectional"))
      (node (ref "U1") (pin "B6") (pinfunction "DP2_B6") (pintype "bidirectional"))
    )
    (net (code "41") (name "Net-(U2-CC1)") (class "Default")
      (node (ref "R2") (pin "1") (pinfunction "1_1") (pintype "passive"))
      (node (ref "U2") (pin "A5") (pinfunction "CC1_A5") (pintype "bidirectional"))
    )
    (net (code "42") (name "Net-(U2-CC2)") (class "Default")
      (node (ref "R1") (pin "1") (pinfunction "1_1") (pintype "passive"))
      (node (ref "U2") (pin "B5") (pinfunction "CC2_B5") (pintype "bidirectional"))
    )
    (net (code "43") (name "VCC") (class "Default")
      (node (ref "C1") (pin "2") (pinfunction "2_2") (pintype "passive"))
      (node (ref "IC2") (pin "3") (pinfunction "VIN_3") (pintype "input"))
      (node (ref "J1") (pin "9") (pinfunction "5V_STDBY_9") (pintype "bidirectional"))
      (node (ref "JP11") (pin "2") (pinfunction "2_2") (pintype "passive"))
      (node (ref "JP3") (pin "2") (pinfunction "2_2") (pintype "passive"))
      (node (ref "LED2") (pin "A") (pinfunction "A_A") (pintype "passive"))
      (node (ref "R14") (pin "2") (pinfunction "2_2") (pintype "passive"))
      (node (ref "U2") (pin "A4B9") (pinfunction "VBUS_A4B9") (pintype "bidirectional"))
      (node (ref "U2") (pin "B4A9") (pinfunction "VBUS_B4A9") (pintype "bidirectional"))
    )
    (net (code "44") (name "unconnected-(IC3-PA5-Pad11)") (class "Default")
      (node (ref "IC3") (pin "11") (pinfunction "PA5_11") (pintype "bidirectional"))
    )
    (net (code "45") (name "unconnected-(J1-NC-Pad20)") (class "Default")
      (node (ref "J1") (pin "20") (pinfunction "NC_20") (pintype "bidirectional"))
    )
    (net (code "46") (name "unconnected-(JP2-Pad2)") (class "Default")
      (node (ref "JP2") (pin "2") (pinfunction "2_2") (pintype "passive"))
    )
    (net (code "47") (name "unconnected-(JP4-Pad2)") (class "Default")
      (node (ref "JP4") (pin "2") (pinfunction "2_2") (pintype "passive"))
    )
    (net (code "48") (name "unconnected-(U1-CC1-PadA5)") (class "Default")
      (node (ref "U1") (pin "A5") (pinfunction "CC1_A5") (pintype "bidirectional"))
    )
    (net (code "49") (name "unconnected-(U1-CC2-PadB5)") (class "Default")
      (node (ref "U1") (pin "B5") (pinfunction "CC2_B5") (pintype "bidirectional"))
    )
    (net (code "50") (name "unconnected-(U1-SBU1-PadA8)") (class "Default")
      (node (ref "U1") (pin "A8") (pinfunction "SBU1_A8") (pintype "bidirectional"))
    )
    (net (code "51") (name "unconnected-(U1-SBU2-PadB8)") (class "Default")
      (node (ref "U1") (pin "B8") (pinfunction "SBU2_B8") (pintype "bidirectional"))
    )
    (net (code "52") (name "unconnected-(U2-SBU1-PadA8)") (class "Default")
      (node (ref "U2") (pin "A8") (pinfunction "SBU1_A8") (pintype "bidirectional"))
    )
    (net (code "53") (name "unconnected-(U2-SBU2-PadB8)") (class "Default")
      (node (ref "U2") (pin "B8") (pinfunction "SBU2_B8") (pintype "bidirectional"))
    )
  )
)
